# HerbScalesch.net
KiCad netlist of a schematic drawn in EAGLE
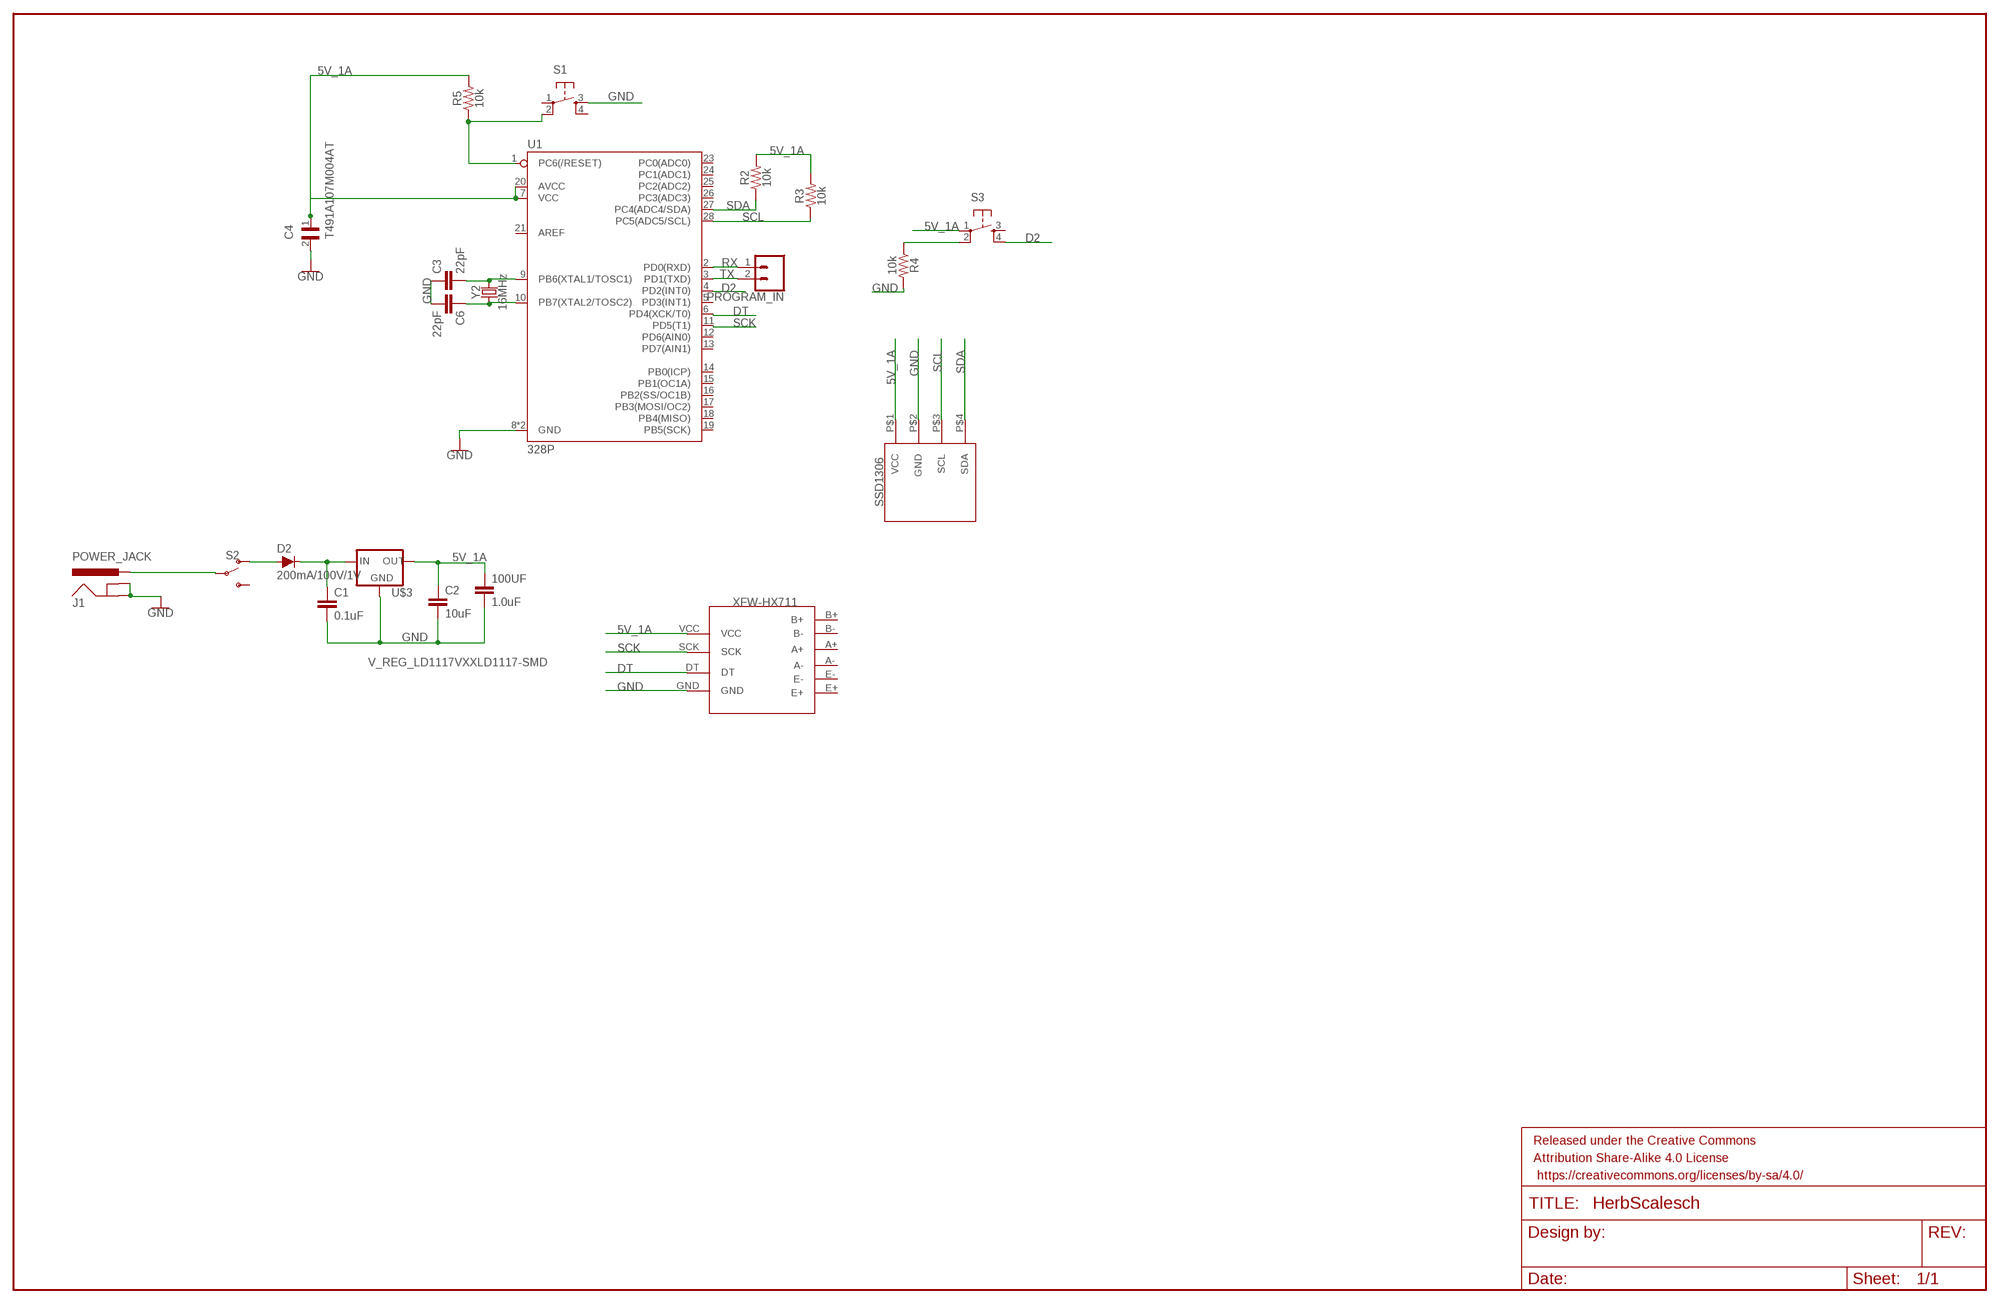
[diagram p0: schematic, sheet 1]

(export (version "E")
  (design (tool "Eeschema 10.0.6"))
  (components
    (comp (ref "100UF")
      (value "1.0uF")
      (footprint "eagle-import:1206")
      (libsource (lib "eagle-import") (part "1.0UF-1206-50V-10%"))
    )
    (comp (ref "C1")
      (value "0.1uF")
      (footprint "eagle-import:0603")
      (libsource (lib "eagle-import") (part "0.1UF-0603-25V-(+80/-20%)"))
    )
    (comp (ref "C2")
      (value "10uF")
      (footprint "eagle-import:0603")
      (libsource (lib "eagle-import") (part "10UF-0603-6.3V-20%"))
    )
    (comp (ref "C3")
      (value "22pF")
      (footprint "eagle-import:CAP-PTH-2.54")
      (libsource (lib "eagle-import") (part "22PF-PTH-2.54MM-200V-5%"))
    )
    (comp (ref "C4")
      (value "T491A107M004AT")
      (footprint "eagle-import:CAPC3216X110N")
      (fields (field (name "MF") "KEMET"))
      (libsource (lib "eagle-import") (part "T491A107M004AT"))
    )
    (comp (ref "C6")
      (value "22pF")
      (footprint "eagle-import:CAP-PTH-2.54")
      (libsource (lib "eagle-import") (part "22PF-PTH-2.54MM-200V-5%"))
    )
    (comp (ref "D2")
      (value "200mA/100V/1V")
      (footprint "eagle-import:DIODE-1N4148")
      (libsource (lib "eagle-import") (part "DIODE-1N4148"))
    )
    (comp (ref "FRAME1")
      (value "FRAME-LEDGER")
      (footprint "eagle-import:CREATIVE_COMMONS")
      (libsource (lib "eagle-import") (part "FRAME-LEDGER"))
    )
    (comp (ref "J1")
      (value "POWER_JACK")
      (footprint "eagle-import:POWER_JACK_PTH")
      (libsource (lib "eagle-import") (part "POWER_JACK"))
    )
    (comp (ref "PROGRAM_IN")
      (value "CONN_02")
      (footprint "eagle-import:1X02")
      (libsource (lib "eagle-import") (part "CONN_02"))
    )
    (comp (ref "R2")
      (value "10k")
      (footprint "eagle-import:AXIAL-0.3")
      (libsource (lib "eagle-import") (part "10KOHM-HORIZ-1/4W-5%"))
    )
    (comp (ref "R3")
      (value "10k")
      (footprint "eagle-import:AXIAL-0.3")
      (libsource (lib "eagle-import") (part "10KOHM-HORIZ-1/4W-5%"))
    )
    (comp (ref "R4")
      (value "10k")
      (footprint "eagle-import:AXIAL-0.3")
      (libsource (lib "eagle-import") (part "10KOHM-HORIZ-1/4W-5%"))
    )
    (comp (ref "R5")
      (value "10k")
      (footprint "eagle-import:AXIAL-0.3")
      (libsource (lib "eagle-import") (part "10KOHM-HORIZ-1/4W-5%"))
    )
    (comp (ref "S1")
      (value "TAC_SWITCHPTH")
      (footprint "eagle-import:TACTILE-PTH")
      (libsource (lib "eagle-import") (part "TAC_SWITCHPTH"))
    )
    (comp (ref "S2")
      (value "SWITCH-SPDT-PTH-11.6X4.0MM")
      (footprint "eagle-import:SWITCH_SPDT_PTH_11.6X4.0MM")
      (libsource (lib "eagle-import") (part "SWITCH-SPDT-PTH-11.6X4.0MM"))
    )
    (comp (ref "S3")
      (value "TAC_SWITCHPTH")
      (footprint "eagle-import:TACTILE-PTH")
      (libsource (lib "eagle-import") (part "TAC_SWITCHPTH"))
    )
    (comp (ref "U$1")
      (value "SSD1306")
      (footprint "eagle-import:SSD1306")
      (libsource (lib "eagle-import") (part "SSD1306"))
    )
    (comp (ref "U$2")
      (value "XFW-HX711")
      (footprint "eagle-import:XFW-HX711")
      (libsource (lib "eagle-import") (part "XFW-HX711"))
    )
    (comp (ref "U$3")
      (value "V_REG_LD1117VXXLD1117-SMD")
      (footprint "eagle-import:SOT223")
      (libsource (lib "eagle-import") (part "V_REG_LD1117VXXLD1117-SMD"))
    )
    (comp (ref "U1")
      (value "328P")
      (footprint "eagle-import:DIP28")
      (libsource (lib "eagle-import") (part "ATMEGA328P_PDIP"))
    )
    (comp (ref "Y2")
      (value "16MHz")
      (footprint "eagle-import:HC49US")
      (libsource (lib "eagle-import") (part "CRYSTAL-16MHZPTH-HC49US"))
    )
  )
  (nets
    (net (code "1") (name "/5V_1A") (class "Default")
      (node (ref "100UF") (pin "1") (pinfunction "1_1") (pintype "passive"))
      (node (ref "C2") (pin "1") (pinfunction "1_1") (pintype "passive"))
      (node (ref "C4") (pin "1") (pinfunction "1_1") (pintype "passive"))
      (node (ref "R2") (pin "P$2") (pinfunction "2_P$2") (pintype "passive"))
      (node (ref "R3") (pin "P$2") (pinfunction "2_P$2") (pintype "passive"))
      (node (ref "R5") (pin "P$2") (pinfunction "2_P$2") (pintype "passive"))
      (node (ref "S3") (pin "1") (pinfunction "1_1") (pintype "passive"))
      (node (ref "U$1") (pin "P$1") (pinfunction "VCC_P$1") (pintype "bidirectional"))
      (node (ref "U$2") (pin "VCC") (pinfunction "VCC_VCC") (pintype "bidirectional"))
      (node (ref "U$3") (pin "2") (pinfunction "OUT_2") (pintype "passive"))
      (node (ref "U1") (pin "20") (pinfunction "AVCC_20") (pintype "bidirectional"))
      (node (ref "U1") (pin "7") (pinfunction "VCC_7") (pintype "bidirectional"))
    )
    (net (code "2") (name "/D2") (class "Default")
      (node (ref "S3") (pin "4") (pinfunction "4_4") (pintype "passive"))
      (node (ref "U1") (pin "4") (pinfunction "PD2(INT0)_4") (pintype "bidirectional"))
    )
    (net (code "3") (name "/DT") (class "Default")
      (node (ref "U$2") (pin "DT") (pinfunction "DT_DT") (pintype "bidirectional"))
      (node (ref "U1") (pin "6") (pinfunction "PD4(XCK/T0)_6") (pintype "bidirectional"))
    )
    (net (code "4") (name "/RX") (class "Default")
      (node (ref "PROGRAM_IN") (pin "1") (pinfunction "1_1") (pintype "passive"))
      (node (ref "U1") (pin "2") (pinfunction "PD0(RXD)_2") (pintype "bidirectional"))
    )
    (net (code "5") (name "/SCK") (class "Default")
      (node (ref "U$2") (pin "SCK") (pinfunction "SCK_SCK") (pintype "bidirectional"))
      (node (ref "U1") (pin "11") (pinfunction "PD5(T1)_11") (pintype "bidirectional"))
    )
    (net (code "6") (name "/SCL") (class "Default")
      (node (ref "R3") (pin "P$1") (pinfunction "1_P$1") (pintype "passive"))
      (node (ref "U$1") (pin "P$3") (pinfunction "SCL_P$3") (pintype "bidirectional"))
      (node (ref "U1") (pin "28") (pinfunction "PC5(ADC5/SCL)_28") (pintype "bidirectional"))
    )
    (net (code "7") (name "/SDA") (class "Default")
      (node (ref "R2") (pin "P$1") (pinfunction "1_P$1") (pintype "passive"))
      (node (ref "U$1") (pin "P$4") (pinfunction "SDA_P$4") (pintype "bidirectional"))
      (node (ref "U1") (pin "27") (pinfunction "PC4(ADC4/SDA)_27") (pintype "bidirectional"))
    )
    (net (code "8") (name "/TX") (class "Default")
      (node (ref "PROGRAM_IN") (pin "2") (pinfunction "2_2") (pintype "passive"))
      (node (ref "U1") (pin "3") (pinfunction "PD1(TXD)_3") (pintype "bidirectional"))
    )
    (net (code "9") (name "GND") (class "Default")
      (node (ref "100UF") (pin "2") (pinfunction "2_2") (pintype "passive"))
      (node (ref "C1") (pin "2") (pinfunction "2_2") (pintype "passive"))
      (node (ref "C2") (pin "2") (pinfunction "2_2") (pintype "passive"))
      (node (ref "C3") (pin "1") (pinfunction "1_1") (pintype "passive"))
      (node (ref "C4") (pin "2") (pinfunction "2_2") (pintype "passive"))
      (node (ref "C6") (pin "2") (pinfunction "2_2") (pintype "passive"))
      (node (ref "J1") (pin "GND") (pinfunction "GND_GND") (pintype "bidirectional"))
      (node (ref "J1") (pin "GNDBREAK") (pinfunction "GNDBREAK_GNDBREAK") (pintype "bidirectional"))
      (node (ref "R4") (pin "P$2") (pinfunction "2_P$2") (pintype "passive"))
      (node (ref "S1") (pin "3") (pinfunction "3_3") (pintype "passive"))
      (node (ref "U$1") (pin "P$2") (pinfunction "GND_P$2") (pintype "bidirectional"))
      (node (ref "U$2") (pin "GND") (pinfunction "GND_GND") (pintype "bidirectional"))
      (node (ref "U$3") (pin "1") (pinfunction "GND_1") (pintype "input"))
      (node (ref "U1") (pin "22") (pinfunction "GND_22") (pintype "bidirectional"))
      (node (ref "U1") (pin "8") (pinfunction "GND_8") (pintype "bidirectional"))
    )
    (net (code "10") (name "Net-(R4-1)") (class "Default")
      (node (ref "R4") (pin "P$1") (pinfunction "1_P$1") (pintype "passive"))
      (node (ref "S3") (pin "2") (pinfunction "2_2") (pintype "passive"))
    )
    (net (code "11") (name "Net-(R5-1)") (class "Default")
      (node (ref "R5") (pin "P$1") (pinfunction "1_P$1") (pintype "passive"))
      (node (ref "S1") (pin "2") (pinfunction "2_2") (pintype "passive"))
      (node (ref "U1") (pin "1") (pinfunction "PC6(/RESET)_1") (pintype "bidirectional"))
    )
    (net (code "12") (name "Net-(S2-O)") (class "Default")
      (node (ref "D2") (pin "A") (pinfunction "A_A") (pintype "passive"))
      (node (ref "S2") (pin "1") (pinfunction "O_1") (pintype "passive"))
    )
    (net (code "13") (name "Net-(S2-P)") (class "Default")
      (node (ref "J1") (pin "PWR") (pinfunction "PWR_PWR") (pintype "bidirectional"))
      (node (ref "S2") (pin "2") (pinfunction "P_2") (pintype "passive"))
    )
    (net (code "14") (name "Net-(U$3-IN)") (class "Default")
      (node (ref "C1") (pin "1") (pinfunction "1_1") (pintype "passive"))
      (node (ref "D2") (pin "C") (pinfunction "C_C") (pintype "passive"))
      (node (ref "U$3") (pin "3") (pinfunction "IN_3") (pintype "input"))
    )
    (net (code "15") (name "Net-(U1-PB6(XTAL1{slash}TOSC1))") (class "Default")
      (node (ref "C3") (pin "2") (pinfunction "2_2") (pintype "passive"))
      (node (ref "U1") (pin "9") (pinfunction "PB6(XTAL1/TOSC1)_9") (pintype "bidirectional"))
      (node (ref "Y2") (pin "2") (pinfunction "2_2") (pintype "passive"))
    )
    (net (code "16") (name "Net-(U1-PB7(XTAL2{slash}TOSC2))") (class "Default")
      (node (ref "C6") (pin "1") (pinfunction "1_1") (pintype "passive"))
      (node (ref "U1") (pin "10") (pinfunction "PB7(XTAL2/TOSC2)_10") (pintype "bidirectional"))
      (node (ref "Y2") (pin "1") (pinfunction "1_1") (pintype "passive"))
    )
    (net (code "17") (name "unconnected-(S1-Pad1)") (class "Default")
      (node (ref "S1") (pin "1") (pinfunction "1_1") (pintype "passive"))
    )
    (net (code "18") (name "unconnected-(S1-Pad4)") (class "Default")
      (node (ref "S1") (pin "4") (pinfunction "4_4") (pintype "passive"))
    )
    (net (code "19") (name "unconnected-(S2-S-Pad3)") (class "Default")
      (node (ref "S2") (pin "3") (pinfunction "S_3") (pintype "passive"))
    )
    (net (code "20") (name "unconnected-(S3-Pad3)") (class "Default")
      (node (ref "S3") (pin "3") (pinfunction "3_3") (pintype "passive"))
    )
    (net (code "21") (name "unconnected-(U$2-PadA+)") (class "Default")
      (node (ref "U$2") (pin "A+") (pinfunction "A+_A+") (pintype "bidirectional"))
    )
    (net (code "22") (name "unconnected-(U$2-PadA-)") (class "Default")
      (node (ref "U$2") (pin "A-") (pinfunction "A-_A-") (pintype "bidirectional"))
    )
    (net (code "23") (name "unconnected-(U$2-PadB+)") (class "Default")
      (node (ref "U$2") (pin "B+") (pinfunction "B+_B+") (pintype "bidirectional"))
    )
    (net (code "24") (name "unconnected-(U$2-PadB-)") (class "Default")
      (node (ref "U$2") (pin "B-") (pinfunction "B-_B-") (pintype "bidirectional"))
    )
    (net (code "25") (name "unconnected-(U$2-PadE+)") (class "Default")
      (node (ref "U$2") (pin "E+") (pinfunction "E+_E+") (pintype "bidirectional"))
    )
    (net (code "26") (name "unconnected-(U$2-PadE-)") (class "Default")
      (node (ref "U$2") (pin "E-") (pinfunction "E-_E-") (pintype "bidirectional"))
    )
    (net (code "27") (name "unconnected-(U1-AREF-Pad21)") (class "Default")
      (node (ref "U1") (pin "21") (pinfunction "AREF_21") (pintype "bidirectional"))
    )
    (net (code "28") (name "unconnected-(U1-PB0(ICP)-Pad14)") (class "Default")
      (node (ref "U1") (pin "14") (pinfunction "PB0(ICP)_14") (pintype "bidirectional"))
    )
    (net (code "29") (name "unconnected-(U1-PB1(OC1A)-Pad15)") (class "Default")
      (node (ref "U1") (pin "15") (pinfunction "PB1(OC1A)_15") (pintype "bidirectional"))
    )
    (net (code "30") (name "unconnected-(U1-PB2(SS{slash}OC1B)-Pad16)") (class "Default")
      (node (ref "U1") (pin "16") (pinfunction "PB2(SS/OC1B)_16") (pintype "bidirectional"))
    )
    (net (code "31") (name "unconnected-(U1-PB3(MOSI{slash}OC2)-Pad17)") (class "Default")
      (node (ref "U1") (pin "17") (pinfunction "PB3(MOSI/OC2)_17") (pintype "bidirectional"))
    )
    (net (code "32") (name "unconnected-(U1-PB4(MISO)-Pad18)") (class "Default")
      (node (ref "U1") (pin "18") (pinfunction "PB4(MISO)_18") (pintype "bidirectional"))
    )
    (net (code "33") (name "unconnected-(U1-PB5(SCK)-Pad19)") (class "Default")
      (node (ref "U1") (pin "19") (pinfunction "PB5(SCK)_19") (pintype "bidirectional"))
    )
    (net (code "34") (name "unconnected-(U1-PC0(ADC0)-Pad23)") (class "Default")
      (node (ref "U1") (pin "23") (pinfunction "PC0(ADC0)_23") (pintype "bidirectional"))
    )
    (net (code "35") (name "unconnected-(U1-PC1(ADC1)-Pad24)") (class "Default")
      (node (ref "U1") (pin "24") (pinfunction "PC1(ADC1)_24") (pintype "bidirectional"))
    )
    (net (code "36") (name "unconnected-(U1-PC2(ADC2)-Pad25)") (class "Default")
      (node (ref "U1") (pin "25") (pinfunction "PC2(ADC2)_25") (pintype "bidirectional"))
    )
    (net (code "37") (name "unconnected-(U1-PC3(ADC3)-Pad26)") (class "Default")
      (node (ref "U1") (pin "26") (pinfunction "PC3(ADC3)_26") (pintype "bidirectional"))
    )
    (net (code "38") (name "unconnected-(U1-PD3(INT1)-Pad5)") (class "Default")
      (node (ref "U1") (pin "5") (pinfunction "PD3(INT1)_5") (pintype "bidirectional"))
    )
    (net (code "39") (name "unconnected-(U1-PD6(AIN0)-Pad12)") (class "Default")
      (node (ref "U1") (pin "12") (pinfunction "PD6(AIN0)_12") (pintype "bidirectional"))
    )
    (net (code "40") (name "unconnected-(U1-PD7(AIN1)-Pad13)") (class "Default")
      (node (ref "U1") (pin "13") (pinfunction "PD7(AIN1)_13") (pintype "bidirectional"))
    )
  )
)
